# Magnet.net
KiCad netlist of a schematic drawn in EAGLE
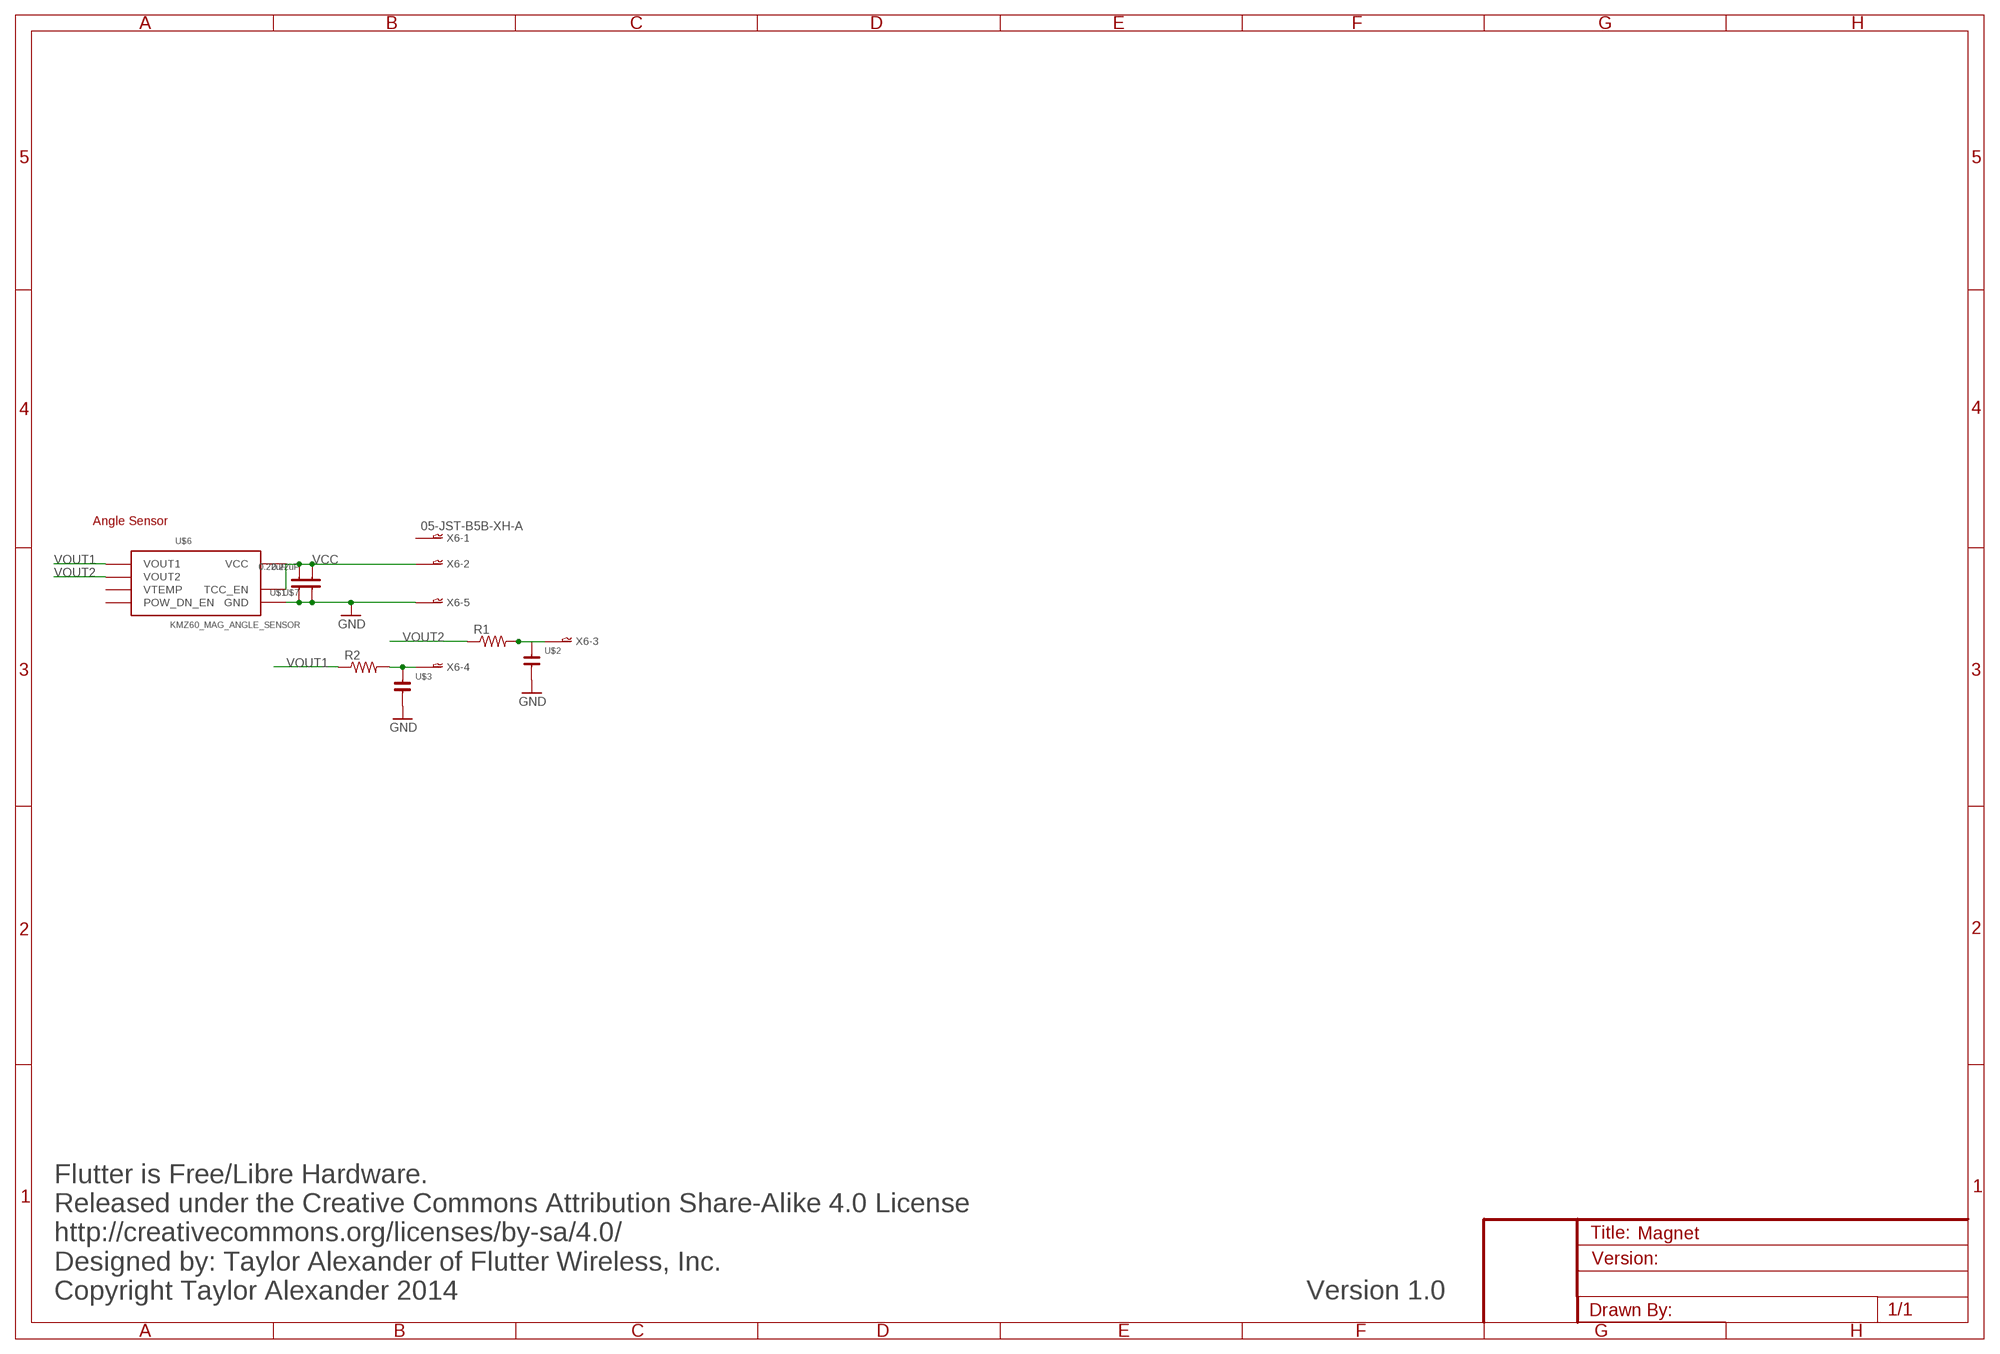
[diagram p0: schematic, sheet 1]

(export (version "E")
  (design (tool "Eeschema 10.0.6"))
  (components
    (comp (ref "R1")
      (value "RESISTOR0603")
      (footprint "eagle-import:0603-RES")
      (libsource (lib "eagle-import") (part "RESISTOR0603"))
    )
    (comp (ref "R2")
      (value "RESISTOR0603")
      (footprint "eagle-import:0603-RES")
      (libsource (lib "eagle-import") (part "RESISTOR0603"))
    )
    (comp (ref "U$1")
      (value "0.22uF")
      (footprint "eagle-import:0808-CAP")
      (libsource (lib "eagle-import") (part "CAPACITOR0805"))
    )
    (comp (ref "U$2")
      (value "CAPACITOR0603-CAP")
      (footprint "eagle-import:0603-CAP")
      (libsource (lib "eagle-import") (part "CAPACITOR0603-CAP"))
    )
    (comp (ref "U$3")
      (value "CAPACITOR0603-CAP")
      (footprint "eagle-import:0603-CAP")
      (libsource (lib "eagle-import") (part "CAPACITOR0603-CAP"))
    )
    (comp (ref "U$6")
      (value "KMZ60_MAG_ANGLE_SENSOR")
      (footprint "eagle-import:SO-8")
      (libsource (lib "eagle-import") (part "KMZ60_MAG_ANGLE_SENSOR"))
    )
    (comp (ref "U$7")
      (value "0.22uF")
      (footprint "eagle-import:0808-CAP")
      (libsource (lib "eagle-import") (part "CAPACITOR0805"))
    )
    (comp (ref "X6")
      (value "05-JST-B5B-XH-A")
      (footprint "eagle-import:B5B-XH")
      (libsource (lib "eagle-import") (part "05-JST-B5B-XH-A"))
    )
  )
  (nets
    (net (code "1") (name "/VCC") (class "Default")
      (node (ref "U$1") (pin "2") (pinfunction "2_2") (pintype "bidirectional"))
      (node (ref "U$6") (pin "P$1") (pinfunction "TCC_EN_P$1") (pintype "bidirectional"))
      (node (ref "U$6") (pin "P$7") (pinfunction "VCC_P$7") (pintype "bidirectional"))
      (node (ref "U$7") (pin "2") (pinfunction "2_2") (pintype "bidirectional"))
      (node (ref "X6") (pin "P$2") (pinfunction "1_P$2") (pintype "passive"))
    )
    (net (code "2") (name "/VOUT1") (class "Default")
      (node (ref "R2") (pin "1") (pinfunction "1_1") (pintype "passive"))
      (node (ref "U$6") (pin "P$2") (pinfunction "VOUT1_P$2") (pintype "bidirectional"))
    )
    (net (code "3") (name "/VOUT2") (class "Default")
      (node (ref "R1") (pin "1") (pinfunction "1_1") (pintype "passive"))
      (node (ref "U$6") (pin "P$4") (pinfunction "VOUT2_P$4") (pintype "bidirectional"))
    )
    (net (code "4") (name "GND") (class "Default")
      (node (ref "U$1") (pin "1") (pinfunction "1_1") (pintype "bidirectional"))
      (node (ref "U$2") (pin "2") (pinfunction "2_2") (pintype "bidirectional"))
      (node (ref "U$3") (pin "2") (pinfunction "2_2") (pintype "bidirectional"))
      (node (ref "U$6") (pin "P$3") (pinfunction "GND_P$3") (pintype "bidirectional"))
      (node (ref "U$6") (pin "P$6") (pinfunction "GND_P$6") (pintype "bidirectional"))
      (node (ref "U$7") (pin "1") (pinfunction "1_1") (pintype "bidirectional"))
      (node (ref "X6") (pin "P$5") (pinfunction "1_P$5") (pintype "passive"))
    )
    (net (code "5") (name "Net-(X6C-1)") (class "Default")
      (node (ref "R1") (pin "2") (pinfunction "2_2") (pintype "passive"))
      (node (ref "U$2") (pin "1") (pinfunction "1_1") (pintype "bidirectional"))
      (node (ref "X6") (pin "P$3") (pinfunction "1_P$3") (pintype "passive"))
    )
    (net (code "6") (name "Net-(X6D-1)") (class "Default")
      (node (ref "R2") (pin "2") (pinfunction "2_2") (pintype "passive"))
      (node (ref "U$3") (pin "1") (pinfunction "1_1") (pintype "bidirectional"))
      (node (ref "X6") (pin "P$4") (pinfunction "1_P$4") (pintype "passive"))
    )
    (net (code "7") (name "unconnected-(U$6-POW_DN_EN-PadP$8)") (class "Default")
      (node (ref "U$6") (pin "P$8") (pinfunction "POW_DN_EN_P$8") (pintype "bidirectional"))
    )
    (net (code "8") (name "unconnected-(U$6-VTEMP-PadP$5)") (class "Default")
      (node (ref "U$6") (pin "P$5") (pinfunction "VTEMP_P$5") (pintype "bidirectional"))
    )
    (net (code "9") (name "unconnected-(X6A-1-PadP$1)") (class "Default")
      (node (ref "X6") (pin "P$1") (pinfunction "1_P$1") (pintype "passive"))
    )
  )
)
